# Diagrama_secuda_rio_NOVA.net
KiCad netlist of a schematic drawn in EAGLE
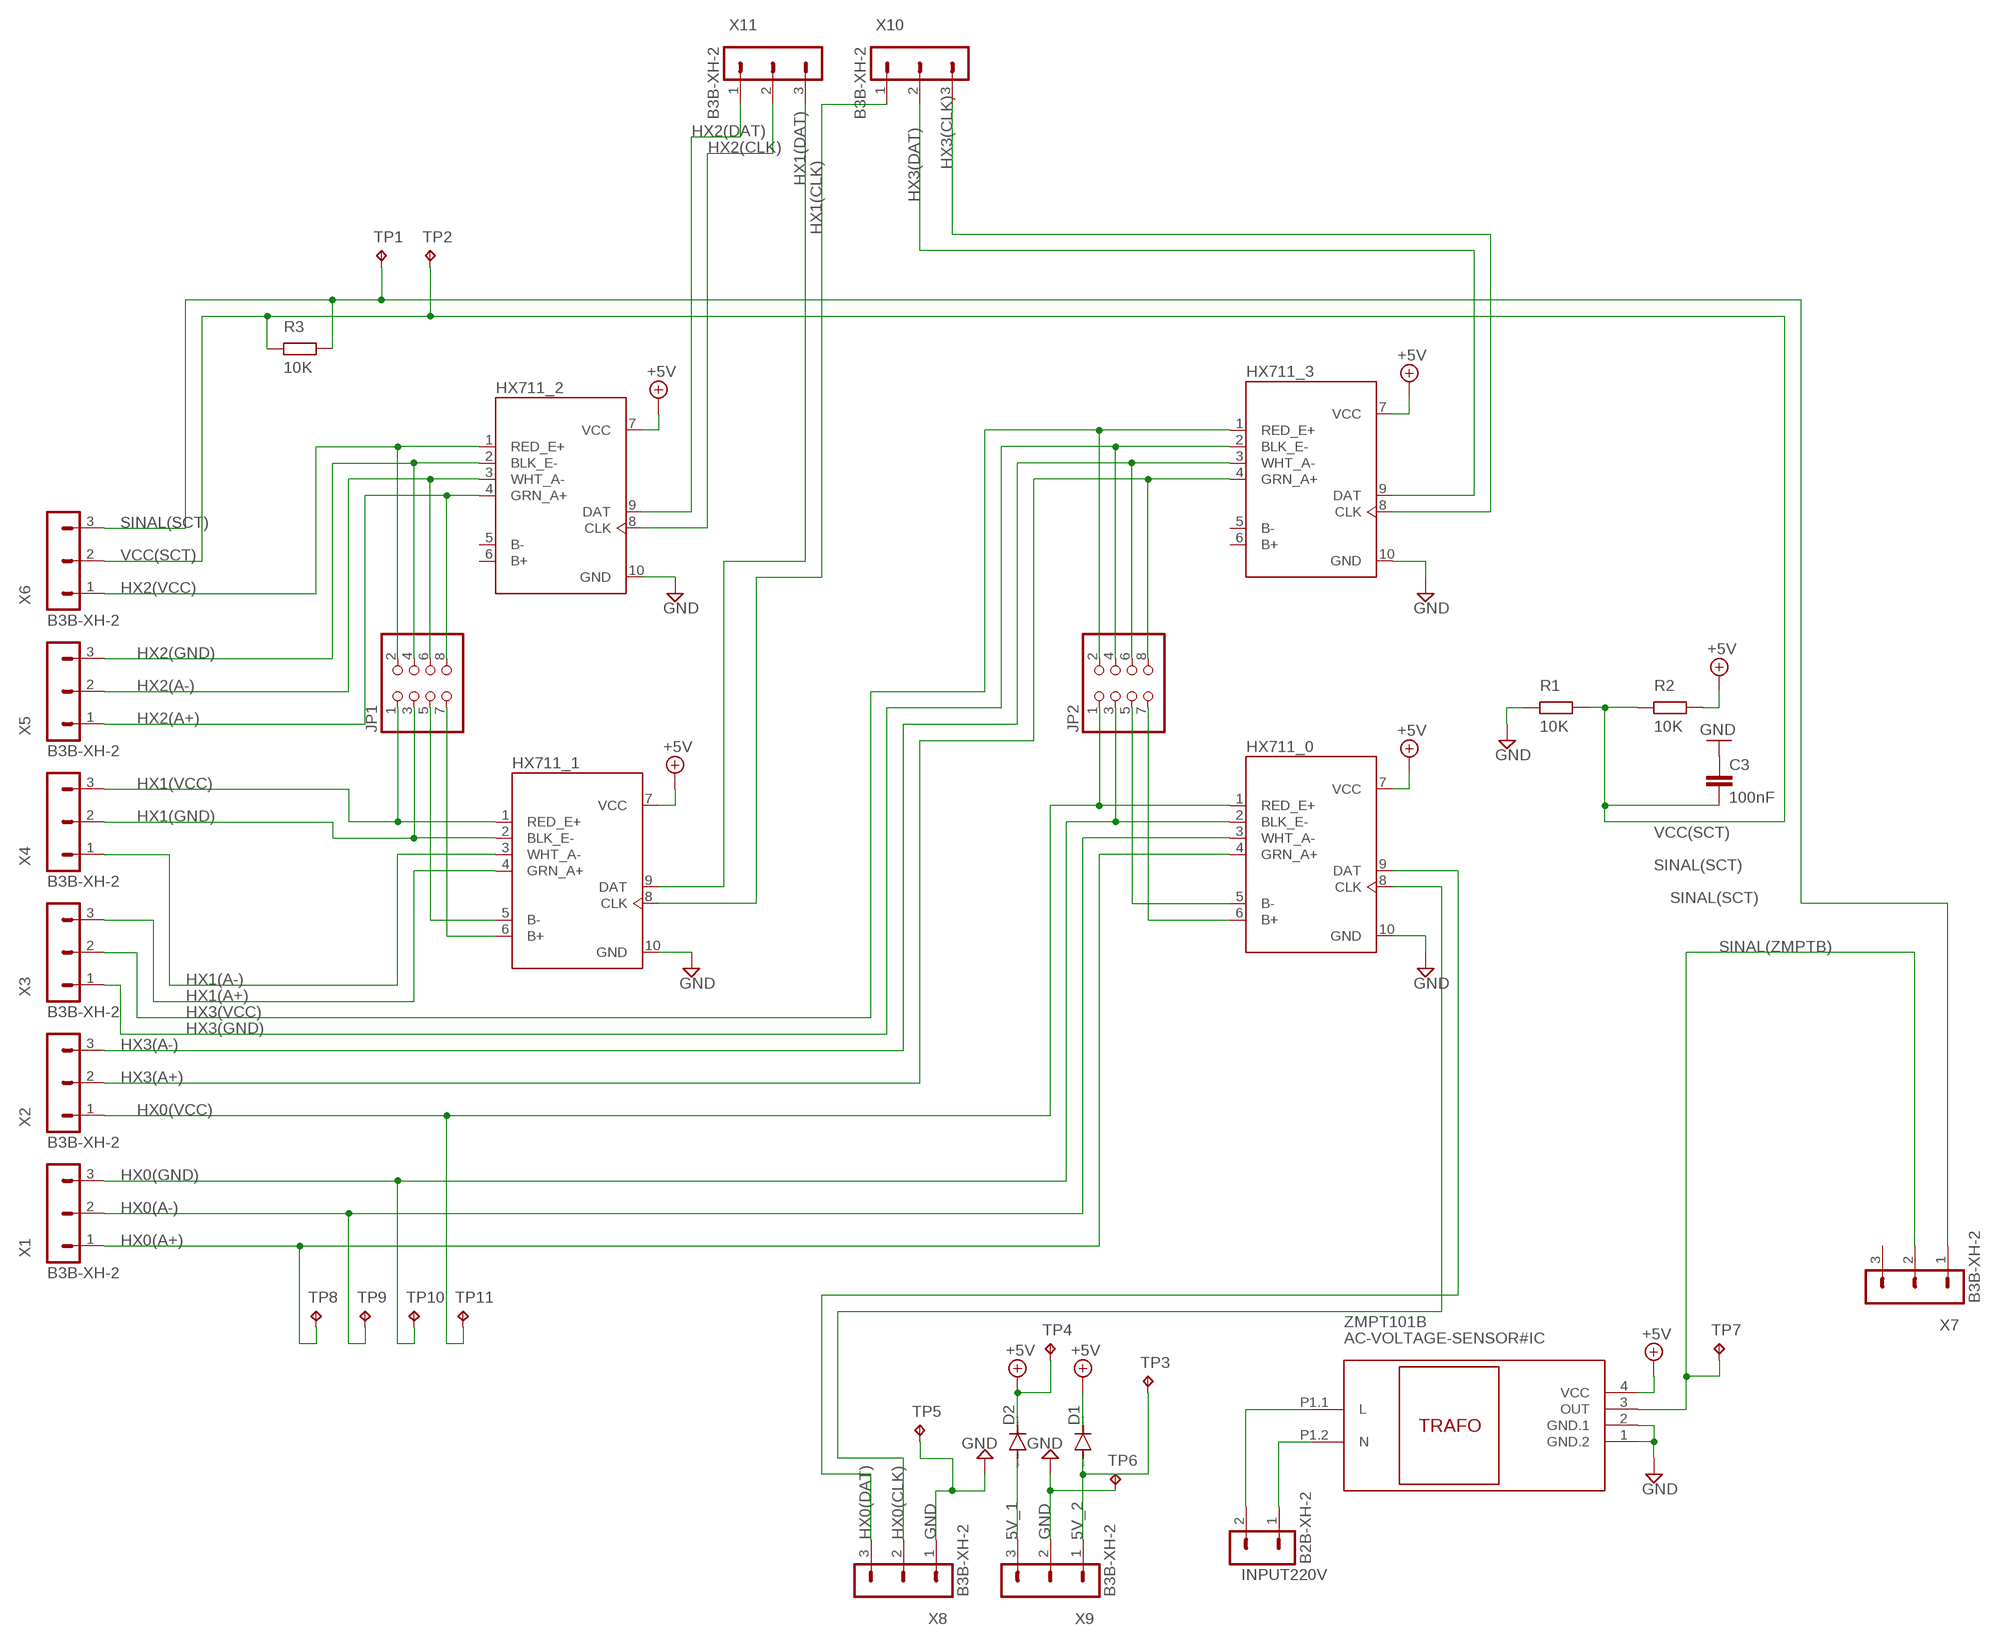
[diagram p0: schematic, sheet 1]

(export (version "E")
  (design (tool "Eeschema 10.0.6"))
  (components
    (comp (ref "C3")
      (value "100nF")
      (footprint "eagle-import:C050-025X075")
      (libsource (lib "eagle-import") (part "C-EU050-025X075"))
    )
    (comp (ref "D1")
      (value "1N4148DO35-7")
      (footprint "eagle-import:DO35-7")
      (fields (field (name "SPICEPREFIX") "D"))
      (libsource (lib "eagle-import") (part "1N4148DO35-7"))
    )
    (comp (ref "D2")
      (value "1")
      (footprint "eagle-import:DO35-7")
      (libsource (lib "eagle-import") (part "1N4148DO35-7"))
    )
    (comp (ref "HX711_0")
      (value "HX711MODULO")
      (footprint "eagle-import:HX711MODULO")
      (fields (field (name "MF") "SparkFun") (field (name "MP") "SEN-13879"))
      (libsource (lib "eagle-import") (part "HX711MODULO"))
    )
    (comp (ref "HX711_1")
      (value "HX711MODULO")
      (footprint "eagle-import:HX711MODULO")
      (fields (field (name "MF") "SparkFun") (field (name "MP") "SEN-13879"))
      (libsource (lib "eagle-import") (part "HX711MODULO"))
    )
    (comp (ref "HX711_2")
      (value "HX711MODULO")
      (footprint "eagle-import:HX711MODULO")
      (fields (field (name "MF") "SparkFun") (field (name "MP") "SEN-13879"))
      (libsource (lib "eagle-import") (part "HX711MODULO"))
    )
    (comp (ref "HX711_3")
      (value "HX711MODULO")
      (footprint "eagle-import:HX711MODULO")
      (fields (field (name "MF") "SparkFun") (field (name "MP") "SEN-13879"))
      (libsource (lib "eagle-import") (part "HX711MODULO"))
    )
    (comp (ref "INPUT220V")
      (value "B2B-XH-2")
      (footprint "eagle-import:B2B-XH-A")
      (libsource (lib "eagle-import") (part "B2B-XH-2"))
    )
    (comp (ref "JP1")
      (value "PINHD-2X4")
      (footprint "eagle-import:2X04")
      (libsource (lib "eagle-import") (part "PINHD-2X4"))
    )
    (comp (ref "JP2")
      (value "PINHD-2X4")
      (footprint "eagle-import:2X04")
      (libsource (lib "eagle-import") (part "PINHD-2X4"))
    )
    (comp (ref "R1")
      (value "10K")
      (footprint "eagle-import:1_4W-0.41K")
      (libsource (lib "eagle-import") (part "1K1/4RESISTOR"))
    )
    (comp (ref "R2")
      (value "10K")
      (footprint "eagle-import:1_4W-0.41K")
      (libsource (lib "eagle-import") (part "1K1/4RESISTOR"))
    )
    (comp (ref "R3")
      (value "10K")
      (footprint "eagle-import:1_4W-0.41K")
      (libsource (lib "eagle-import") (part "1K1/4RESISTOR"))
    )
    (comp (ref "TP1")
      (value "TPB1,27")
      (footprint "eagle-import:B1,27")
      (libsource (lib "eagle-import") (part "TPB1,27"))
    )
    (comp (ref "TP2")
      (value "TPB1,27")
      (footprint "eagle-import:B1,27")
      (libsource (lib "eagle-import") (part "TPB1,27"))
    )
    (comp (ref "TP3")
      (value "TPB1,27")
      (footprint "eagle-import:B1,27")
      (libsource (lib "eagle-import") (part "TPB1,27"))
    )
    (comp (ref "TP4")
      (value "TPB1,27")
      (footprint "eagle-import:B1,27")
      (libsource (lib "eagle-import") (part "TPB1,27"))
    )
    (comp (ref "TP5")
      (value "TPB1,27")
      (footprint "eagle-import:B1,27")
      (libsource (lib "eagle-import") (part "TPB1,27"))
    )
    (comp (ref "TP6")
      (value "TPB1,27")
      (footprint "eagle-import:B1,27")
      (libsource (lib "eagle-import") (part "TPB1,27"))
    )
    (comp (ref "TP7")
      (value "TPB1,27")
      (footprint "eagle-import:B1,27")
      (libsource (lib "eagle-import") (part "TPB1,27"))
    )
    (comp (ref "TP8")
      (value "TPB1,27")
      (footprint "eagle-import:B1,27")
      (libsource (lib "eagle-import") (part "TPB1,27"))
    )
    (comp (ref "TP9")
      (value "TPB1,27")
      (footprint "eagle-import:B1,27")
      (libsource (lib "eagle-import") (part "TPB1,27"))
    )
    (comp (ref "TP10")
      (value "TPB1,27")
      (footprint "eagle-import:B1,27")
      (libsource (lib "eagle-import") (part "TPB1,27"))
    )
    (comp (ref "TP11")
      (value "TPB1,27")
      (footprint "eagle-import:B1,27")
      (libsource (lib "eagle-import") (part "TPB1,27"))
    )
    (comp (ref "X1")
      (value "B3B-XH-2")
      (footprint "eagle-import:B3B-XH-A")
      (libsource (lib "eagle-import") (part "B3B-XH-2"))
    )
    (comp (ref "X2")
      (value "B3B-XH-2")
      (footprint "eagle-import:B3B-XH-A")
      (libsource (lib "eagle-import") (part "B3B-XH-2"))
    )
    (comp (ref "X3")
      (value "B3B-XH-2")
      (footprint "eagle-import:B3B-XH-A")
      (libsource (lib "eagle-import") (part "B3B-XH-2"))
    )
    (comp (ref "X4")
      (value "B3B-XH-2")
      (footprint "eagle-import:B3B-XH-A")
      (libsource (lib "eagle-import") (part "B3B-XH-2"))
    )
    (comp (ref "X5")
      (value "B3B-XH-2")
      (footprint "eagle-import:B3B-XH-A")
      (libsource (lib "eagle-import") (part "B3B-XH-2"))
    )
    (comp (ref "X6")
      (value "B3B-XH-2")
      (footprint "eagle-import:B3B-XH-A")
      (libsource (lib "eagle-import") (part "B3B-XH-2"))
    )
    (comp (ref "X7")
      (value "B3B-XH-2")
      (footprint "eagle-import:B3B-XH-A")
      (libsource (lib "eagle-import") (part "B3B-XH-2"))
    )
    (comp (ref "X8")
      (value "B3B-XH-2")
      (footprint "eagle-import:B3B-XH-A")
      (libsource (lib "eagle-import") (part "B3B-XH-2"))
    )
    (comp (ref "X9")
      (value "B3B-XH-2")
      (footprint "eagle-import:B3B-XH-A")
      (libsource (lib "eagle-import") (part "B3B-XH-2"))
    )
    (comp (ref "X10")
      (value "B3B-XH-2")
      (footprint "eagle-import:B3B-XH-A")
      (libsource (lib "eagle-import") (part "B3B-XH-2"))
    )
    (comp (ref "X11")
      (value "B3B-XH-2")
      (footprint "eagle-import:B3B-XH-A")
      (libsource (lib "eagle-import") (part "B3B-XH-2"))
    )
    (comp (ref "ZMPT101B")
      (value "AC-VOLTAGE-SENSOR#IC")
      (footprint "eagle-import:AC-VOLTAGE-SENSOR#IC")
      (libsource (lib "eagle-import") (part "AC-VOLTAGE-SENSOR#IC"))
    )
  )
  (nets
    (net (code "1") (name "+5V") (class "Default")
      (node (ref "D1") (pin "C") (pinfunction "C_C") (pintype "passive"))
      (node (ref "D2") (pin "C") (pinfunction "C_C") (pintype "passive"))
      (node (ref "HX711_0") (pin "7") (pinfunction "VCC_7") (pintype "power_in"))
      (node (ref "HX711_1") (pin "7") (pinfunction "VCC_7") (pintype "power_in"))
      (node (ref "HX711_2") (pin "7") (pinfunction "VCC_7") (pintype "power_in"))
      (node (ref "HX711_3") (pin "7") (pinfunction "VCC_7") (pintype "power_in"))
      (node (ref "R2") (pin "2") (pinfunction "2_2") (pintype "passive"))
      (node (ref "TP4") (pin "TP") (pinfunction "TP_TP") (pintype "input"))
      (node (ref "ZMPT101B") (pin "4") (pinfunction "VCC_4") (pintype "power_in"))
    )
    (net (code "2") (name "/5V_1") (class "Default")
      (node (ref "D2") (pin "A") (pinfunction "A_A") (pintype "passive"))
      (node (ref "X9") (pin "3") (pinfunction "3_3") (pintype "passive"))
    )
    (net (code "3") (name "/5V_2") (class "Default")
      (node (ref "D1") (pin "A") (pinfunction "A_A") (pintype "passive"))
      (node (ref "TP3") (pin "TP") (pinfunction "TP_TP") (pintype "input"))
      (node (ref "X9") (pin "1") (pinfunction "1_1") (pintype "passive"))
    )
    (net (code "4") (name "/HX0(A+)") (class "Default")
      (node (ref "HX711_0") (pin "4") (pinfunction "GRN_A+_4") (pintype "input"))
      (node (ref "TP8") (pin "TP") (pinfunction "TP_TP") (pintype "input"))
      (node (ref "X1") (pin "1") (pinfunction "1_1") (pintype "passive"))
    )
    (net (code "5") (name "/HX0(A-)") (class "Default")
      (node (ref "HX711_0") (pin "3") (pinfunction "WHT_A-_3") (pintype "input"))
      (node (ref "TP9") (pin "TP") (pinfunction "TP_TP") (pintype "input"))
      (node (ref "X1") (pin "2") (pinfunction "2_2") (pintype "passive"))
    )
    (net (code "6") (name "/HX0(CLK)") (class "Default")
      (node (ref "HX711_0") (pin "8") (pinfunction "CLK_8") (pintype "input"))
      (node (ref "X8") (pin "2") (pinfunction "2_2") (pintype "passive"))
    )
    (net (code "7") (name "/HX0(DAT)") (class "Default")
      (node (ref "HX711_0") (pin "9") (pinfunction "DAT_9") (pintype "output"))
      (node (ref "X8") (pin "3") (pinfunction "3_3") (pintype "passive"))
    )
    (net (code "8") (name "/HX0(GND)") (class "Default")
      (node (ref "HX711_0") (pin "2") (pinfunction "BLK_E-_2") (pintype "bidirectional"))
      (node (ref "JP2") (pin "3") (pinfunction "3_3") (pintype "passive"))
      (node (ref "TP10") (pin "TP") (pinfunction "TP_TP") (pintype "input"))
      (node (ref "X1") (pin "3") (pinfunction "3_3") (pintype "passive"))
    )
    (net (code "9") (name "/HX0(VCC)") (class "Default")
      (node (ref "HX711_0") (pin "1") (pinfunction "RED_E+_1") (pintype "bidirectional"))
      (node (ref "JP2") (pin "1") (pinfunction "1_1") (pintype "passive"))
      (node (ref "TP11") (pin "TP") (pinfunction "TP_TP") (pintype "input"))
      (node (ref "X2") (pin "1") (pinfunction "1_1") (pintype "passive"))
    )
    (net (code "10") (name "/HX1(A+)") (class "Default")
      (node (ref "HX711_1") (pin "4") (pinfunction "GRN_A+_4") (pintype "input"))
      (node (ref "X3") (pin "3") (pinfunction "3_3") (pintype "passive"))
    )
    (net (code "11") (name "/HX1(A-)") (class "Default")
      (node (ref "HX711_1") (pin "3") (pinfunction "WHT_A-_3") (pintype "input"))
      (node (ref "X4") (pin "1") (pinfunction "1_1") (pintype "passive"))
    )
    (net (code "12") (name "/HX1(CLK)") (class "Default")
      (node (ref "HX711_1") (pin "8") (pinfunction "CLK_8") (pintype "input"))
      (node (ref "X10") (pin "1") (pinfunction "1_1") (pintype "passive"))
    )
    (net (code "13") (name "/HX1(DAT)") (class "Default")
      (node (ref "HX711_1") (pin "9") (pinfunction "DAT_9") (pintype "output"))
      (node (ref "X11") (pin "3") (pinfunction "3_3") (pintype "passive"))
    )
    (net (code "14") (name "/HX1(GND)") (class "Default")
      (node (ref "HX711_1") (pin "2") (pinfunction "BLK_E-_2") (pintype "bidirectional"))
      (node (ref "JP1") (pin "3") (pinfunction "3_3") (pintype "passive"))
      (node (ref "X4") (pin "2") (pinfunction "2_2") (pintype "passive"))
    )
    (net (code "15") (name "/HX1(VCC)") (class "Default")
      (node (ref "HX711_1") (pin "1") (pinfunction "RED_E+_1") (pintype "bidirectional"))
      (node (ref "JP1") (pin "1") (pinfunction "1_1") (pintype "passive"))
      (node (ref "X4") (pin "3") (pinfunction "3_3") (pintype "passive"))
    )
    (net (code "16") (name "/HX2(A+)") (class "Default")
      (node (ref "HX711_2") (pin "4") (pinfunction "GRN_A+_4") (pintype "input"))
      (node (ref "JP1") (pin "8") (pinfunction "8_8") (pintype "passive"))
      (node (ref "X5") (pin "1") (pinfunction "1_1") (pintype "passive"))
    )
    (net (code "17") (name "/HX2(A-)") (class "Default")
      (node (ref "HX711_2") (pin "3") (pinfunction "WHT_A-_3") (pintype "input"))
      (node (ref "JP1") (pin "6") (pinfunction "6_6") (pintype "passive"))
      (node (ref "X5") (pin "2") (pinfunction "2_2") (pintype "passive"))
    )
    (net (code "18") (name "/HX2(CLK)") (class "Default")
      (node (ref "HX711_2") (pin "8") (pinfunction "CLK_8") (pintype "input"))
      (node (ref "X11") (pin "2") (pinfunction "2_2") (pintype "passive"))
    )
    (net (code "19") (name "/HX2(DAT)") (class "Default")
      (node (ref "HX711_2") (pin "9") (pinfunction "DAT_9") (pintype "output"))
      (node (ref "X11") (pin "1") (pinfunction "1_1") (pintype "passive"))
    )
    (net (code "20") (name "/HX2(GND)") (class "Default")
      (node (ref "HX711_2") (pin "2") (pinfunction "BLK_E-_2") (pintype "bidirectional"))
      (node (ref "JP1") (pin "4") (pinfunction "4_4") (pintype "passive"))
      (node (ref "X5") (pin "3") (pinfunction "3_3") (pintype "passive"))
    )
    (net (code "21") (name "/HX2(VCC)") (class "Default")
      (node (ref "HX711_2") (pin "1") (pinfunction "RED_E+_1") (pintype "bidirectional"))
      (node (ref "JP1") (pin "2") (pinfunction "2_2") (pintype "passive"))
      (node (ref "X6") (pin "1") (pinfunction "1_1") (pintype "passive"))
    )
    (net (code "22") (name "/HX3(A+)") (class "Default")
      (node (ref "HX711_3") (pin "4") (pinfunction "GRN_A+_4") (pintype "input"))
      (node (ref "JP2") (pin "8") (pinfunction "8_8") (pintype "passive"))
      (node (ref "X2") (pin "2") (pinfunction "2_2") (pintype "passive"))
    )
    (net (code "23") (name "/HX3(A-)") (class "Default")
      (node (ref "HX711_3") (pin "3") (pinfunction "WHT_A-_3") (pintype "input"))
      (node (ref "JP2") (pin "6") (pinfunction "6_6") (pintype "passive"))
      (node (ref "X2") (pin "3") (pinfunction "3_3") (pintype "passive"))
    )
    (net (code "24") (name "/HX3(CLK)") (class "Default")
      (node (ref "HX711_3") (pin "8") (pinfunction "CLK_8") (pintype "input"))
      (node (ref "X10") (pin "3") (pinfunction "3_3") (pintype "passive"))
    )
    (net (code "25") (name "/HX3(DAT)") (class "Default")
      (node (ref "HX711_3") (pin "9") (pinfunction "DAT_9") (pintype "output"))
      (node (ref "X10") (pin "2") (pinfunction "2_2") (pintype "passive"))
    )
    (net (code "26") (name "/HX3(GND)") (class "Default")
      (node (ref "HX711_3") (pin "2") (pinfunction "BLK_E-_2") (pintype "bidirectional"))
      (node (ref "JP2") (pin "4") (pinfunction "4_4") (pintype "passive"))
      (node (ref "X3") (pin "1") (pinfunction "1_1") (pintype "passive"))
    )
    (net (code "27") (name "/HX3(VCC)") (class "Default")
      (node (ref "HX711_3") (pin "1") (pinfunction "RED_E+_1") (pintype "bidirectional"))
      (node (ref "JP2") (pin "2") (pinfunction "2_2") (pintype "passive"))
      (node (ref "X3") (pin "2") (pinfunction "2_2") (pintype "passive"))
    )
    (net (code "28") (name "/SINAL(SCT)") (class "Default")
      (node (ref "R3") (pin "2") (pinfunction "2_2") (pintype "passive"))
      (node (ref "TP1") (pin "TP") (pinfunction "TP_TP") (pintype "input"))
      (node (ref "X6") (pin "3") (pinfunction "3_3") (pintype "passive"))
      (node (ref "X7") (pin "1") (pinfunction "1_1") (pintype "passive"))
    )
    (net (code "29") (name "/SINAL(ZMPTB)") (class "Default")
      (node (ref "TP7") (pin "TP") (pinfunction "TP_TP") (pintype "input"))
      (node (ref "X7") (pin "2") (pinfunction "2_2") (pintype "passive"))
      (node (ref "ZMPT101B") (pin "3") (pinfunction "OUT_3") (pintype "output"))
    )
    (net (code "30") (name "/VCC(SCT)") (class "Default")
      (node (ref "C3") (pin "2") (pinfunction "2_2") (pintype "passive"))
      (node (ref "R1") (pin "2") (pinfunction "2_2") (pintype "passive"))
      (node (ref "R2") (pin "1") (pinfunction "1_1") (pintype "passive"))
      (node (ref "R3") (pin "1") (pinfunction "1_1") (pintype "passive"))
      (node (ref "TP2") (pin "TP") (pinfunction "TP_TP") (pintype "input"))
      (node (ref "X6") (pin "2") (pinfunction "2_2") (pintype "passive"))
    )
    (net (code "31") (name "GND") (class "Default")
      (node (ref "C3") (pin "1") (pinfunction "1_1") (pintype "passive"))
      (node (ref "HX711_0") (pin "10") (pinfunction "GND_10") (pintype "power_in"))
      (node (ref "HX711_1") (pin "10") (pinfunction "GND_10") (pintype "power_in"))
      (node (ref "HX711_2") (pin "10") (pinfunction "GND_10") (pintype "power_in"))
      (node (ref "HX711_3") (pin "10") (pinfunction "GND_10") (pintype "power_in"))
      (node (ref "R1") (pin "1") (pinfunction "1_1") (pintype "passive"))
      (node (ref "TP5") (pin "TP") (pinfunction "TP_TP") (pintype "input"))
      (node (ref "TP6") (pin "TP") (pinfunction "TP_TP") (pintype "input"))
      (node (ref "X8") (pin "1") (pinfunction "1_1") (pintype "passive"))
      (node (ref "X9") (pin "2") (pinfunction "2_2") (pintype "passive"))
      (node (ref "ZMPT101B") (pin "1") (pinfunction "GND.2_1") (pintype "power_in"))
      (node (ref "ZMPT101B") (pin "2") (pinfunction "GND.1_2") (pintype "power_in"))
    )
    (net (code "32") (name "Net-(HX711_0-B+)") (class "Default")
      (node (ref "HX711_0") (pin "6") (pinfunction "B+_6") (pintype "input"))
      (node (ref "JP2") (pin "7") (pinfunction "7_7") (pintype "passive"))
    )
    (net (code "33") (name "Net-(HX711_0-B-)") (class "Default")
      (node (ref "HX711_0") (pin "5") (pinfunction "B-_5") (pintype "input"))
      (node (ref "JP2") (pin "5") (pinfunction "5_5") (pintype "passive"))
    )
    (net (code "34") (name "Net-(HX711_1-B+)") (class "Default")
      (node (ref "HX711_1") (pin "6") (pinfunction "B+_6") (pintype "input"))
      (node (ref "JP1") (pin "7") (pinfunction "7_7") (pintype "passive"))
    )
    (net (code "35") (name "Net-(HX711_1-B-)") (class "Default")
      (node (ref "HX711_1") (pin "5") (pinfunction "B-_5") (pintype "input"))
      (node (ref "JP1") (pin "5") (pinfunction "5_5") (pintype "passive"))
    )
    (net (code "36") (name "Net-(ZMPT101B-L)") (class "Default")
      (node (ref "INPUT220V") (pin "2") (pinfunction "2_2") (pintype "passive"))
      (node (ref "ZMPT101B") (pin "P1.1") (pinfunction "L_P1.1") (pintype "passive"))
    )
    (net (code "37") (name "Net-(ZMPT101B-N)") (class "Default")
      (node (ref "INPUT220V") (pin "1") (pinfunction "1_1") (pintype "passive"))
      (node (ref "ZMPT101B") (pin "P1.2") (pinfunction "N_P1.2") (pintype "passive"))
    )
    (net (code "38") (name "unconnected-(HX711_2-B+-Pad6)") (class "Default")
      (node (ref "HX711_2") (pin "6") (pinfunction "B+_6") (pintype "input"))
    )
    (net (code "39") (name "unconnected-(HX711_2-B--Pad5)") (class "Default")
      (node (ref "HX711_2") (pin "5") (pinfunction "B-_5") (pintype "input"))
    )
    (net (code "40") (name "unconnected-(HX711_3-B+-Pad6)") (class "Default")
      (node (ref "HX711_3") (pin "6") (pinfunction "B+_6") (pintype "input"))
    )
    (net (code "41") (name "unconnected-(HX711_3-B--Pad5)") (class "Default")
      (node (ref "HX711_3") (pin "5") (pinfunction "B-_5") (pintype "input"))
    )
    (net (code "42") (name "unconnected-(X7-Pad3)") (class "Default")
      (node (ref "X7") (pin "3") (pinfunction "3_3") (pintype "passive"))
    )
  )
)
